# M162.net
KiCad netlist of a schematic drawn in EAGLE
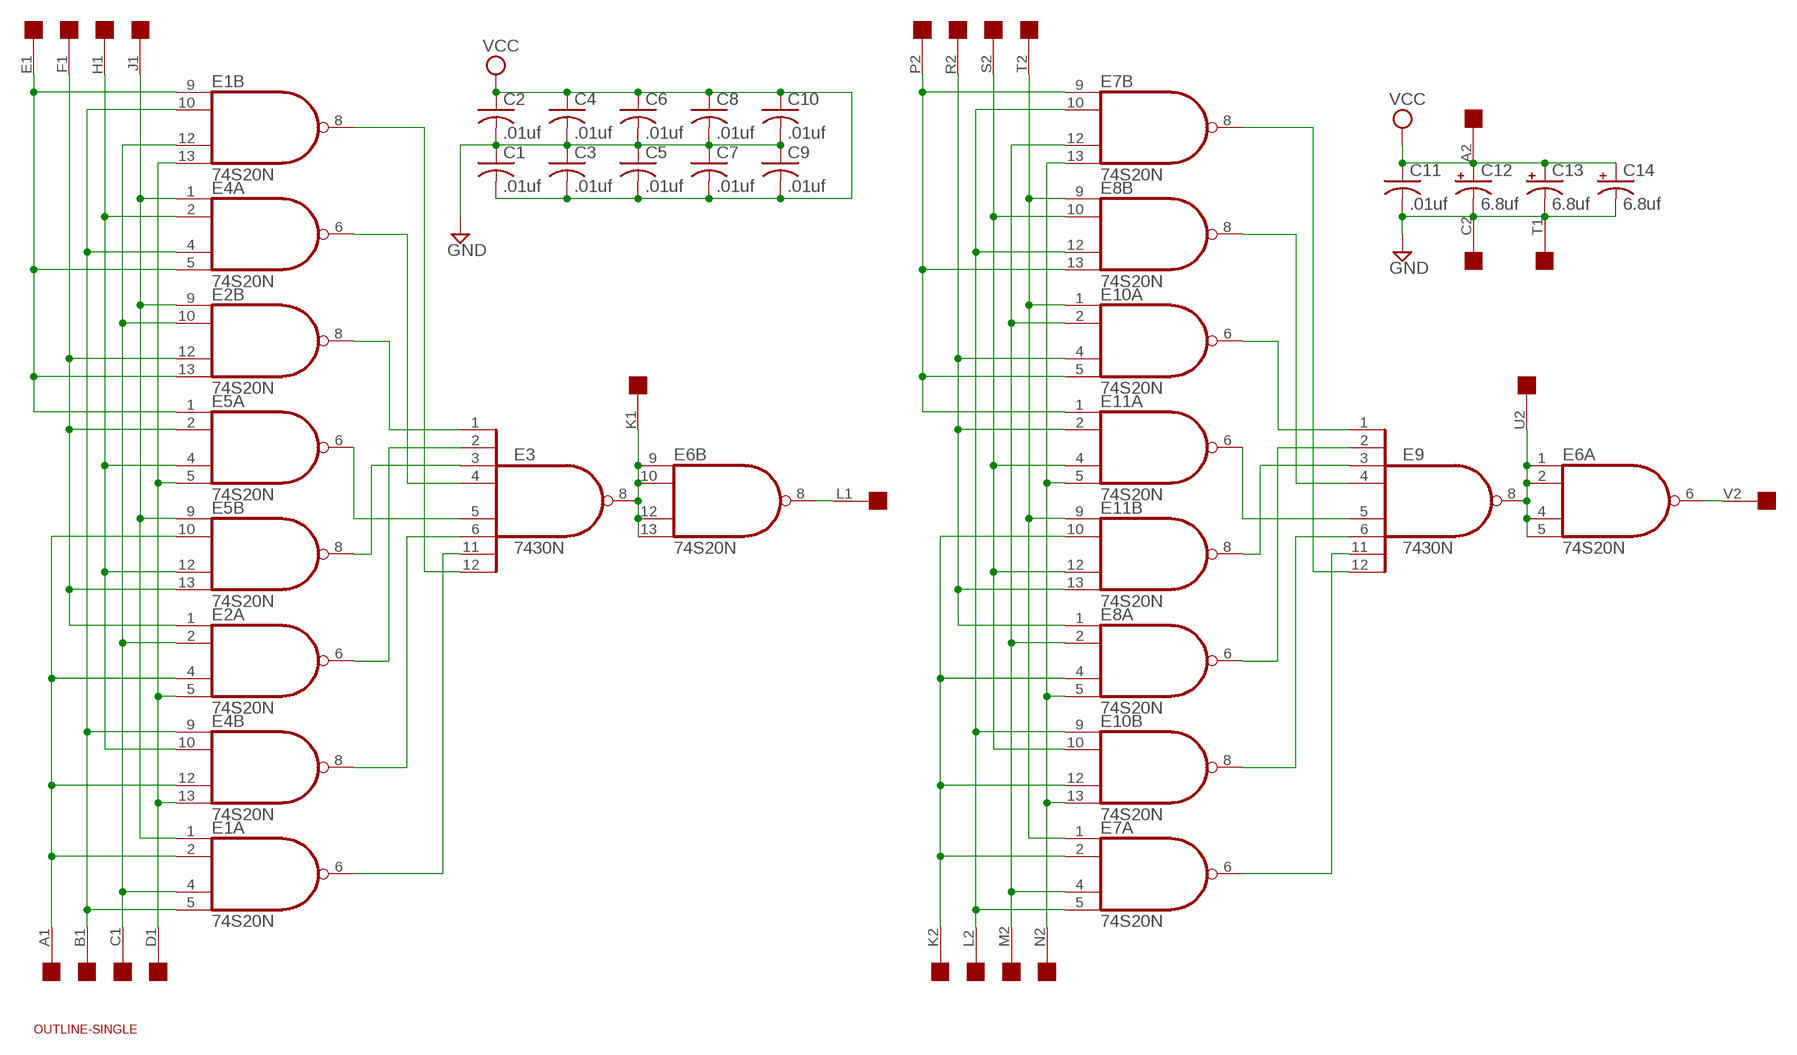
[diagram p0: schematic, sheet 1]

(export (version "E")
  (design (tool "Eeschema 10.0.6"))
  (components
    (comp (ref "C1")
      (value ".01uf")
      (footprint "eagle-import:C050-025X075")
      (libsource (lib "eagle-import") (part "C-US050-025X075"))
    )
    (comp (ref "C2")
      (value ".01uf")
      (footprint "eagle-import:C050-025X075")
      (libsource (lib "eagle-import") (part "C-US050-025X075"))
    )
    (comp (ref "C3")
      (value ".01uf")
      (footprint "eagle-import:C050-025X075")
      (libsource (lib "eagle-import") (part "C-US050-025X075"))
    )
    (comp (ref "C4")
      (value ".01uf")
      (footprint "eagle-import:C050-025X075")
      (libsource (lib "eagle-import") (part "C-US050-025X075"))
    )
    (comp (ref "C5")
      (value ".01uf")
      (footprint "eagle-import:C050-025X075")
      (libsource (lib "eagle-import") (part "C-US050-025X075"))
    )
    (comp (ref "C6")
      (value ".01uf")
      (footprint "eagle-import:C050-025X075")
      (libsource (lib "eagle-import") (part "C-US050-025X075"))
    )
    (comp (ref "C7")
      (value ".01uf")
      (footprint "eagle-import:C050-025X075")
      (libsource (lib "eagle-import") (part "C-US050-025X075"))
    )
    (comp (ref "C8")
      (value ".01uf")
      (footprint "eagle-import:C050-025X075")
      (libsource (lib "eagle-import") (part "C-US050-025X075"))
    )
    (comp (ref "C9")
      (value ".01uf")
      (footprint "eagle-import:C050-025X075")
      (libsource (lib "eagle-import") (part "C-US050-025X075"))
    )
    (comp (ref "C10")
      (value ".01uf")
      (footprint "eagle-import:C050-025X075")
      (libsource (lib "eagle-import") (part "C-US050-025X075"))
    )
    (comp (ref "C11")
      (value ".01uf")
      (footprint "eagle-import:C050-025X075")
      (libsource (lib "eagle-import") (part "C-US050-025X075"))
    )
    (comp (ref "C12")
      (value "6.8uf")
      (footprint "eagle-import:E22-6")
      (libsource (lib "eagle-import") (part "CPOL-USE22-6AXIAL"))
    )
    (comp (ref "C13")
      (value "6.8uf")
      (footprint "eagle-import:E22-6")
      (libsource (lib "eagle-import") (part "CPOL-USE22-6AXIAL"))
    )
    (comp (ref "C14")
      (value "6.8uf")
      (footprint "eagle-import:E22-6")
      (libsource (lib "eagle-import") (part "CPOL-USE22-6AXIAL"))
    )
    (comp (ref "E1")
      (value "74S20N")
      (footprint "eagle-import:DIL14")
      (libsource (lib "eagle-import") (part "7420NS"))
    )
    (comp (ref "E2")
      (value "74S20N")
      (footprint "eagle-import:DIL14")
      (libsource (lib "eagle-import") (part "7420NS"))
    )
    (comp (ref "E3")
      (value "7430N")
      (footprint "eagle-import:DIL14")
      (libsource (lib "eagle-import") (part "7430N"))
    )
    (comp (ref "E4")
      (value "74S20N")
      (footprint "eagle-import:DIL14")
      (libsource (lib "eagle-import") (part "7420NS"))
    )
    (comp (ref "E5")
      (value "74S20N")
      (footprint "eagle-import:DIL14")
      (libsource (lib "eagle-import") (part "7420NS"))
    )
    (comp (ref "E6")
      (value "74S20N")
      (footprint "eagle-import:DIL14")
      (libsource (lib "eagle-import") (part "7420NS"))
    )
    (comp (ref "E7")
      (value "74S20N")
      (footprint "eagle-import:DIL14")
      (libsource (lib "eagle-import") (part "7420NS"))
    )
    (comp (ref "E8")
      (value "74S20N")
      (footprint "eagle-import:DIL14")
      (libsource (lib "eagle-import") (part "7420NS"))
    )
    (comp (ref "E9")
      (value "7430N")
      (footprint "eagle-import:DIL14")
      (libsource (lib "eagle-import") (part "7430N"))
    )
    (comp (ref "E10")
      (value "74S20N")
      (footprint "eagle-import:DIL14")
      (libsource (lib "eagle-import") (part "7420NS"))
    )
    (comp (ref "E11")
      (value "74S20N")
      (footprint "eagle-import:DIL14")
      (libsource (lib "eagle-import") (part "7420NS"))
    )
    (comp (ref "U$1")
      (value "OUTLINE-SINGLE")
      (footprint "eagle-import:SINGLE")
      (libsource (lib "eagle-import") (part "OUTLINE-SINGLE"))
    )
    (comp (ref "U$2")
      (value "EDGE-2CONNECTOR")
      (footprint "eagle-import:EDGE-CON2")
      (libsource (lib "eagle-import") (part "EDGE-2CONNECTOR"))
    )
  )
  (nets
    (net (code "1") (name "GND") (class "Default")
      (node (ref "C1") (pin "1") (pinfunction "1_1") (pintype "passive"))
      (node (ref "C10") (pin "2") (pinfunction "2_2") (pintype "passive"))
      (node (ref "C11") (pin "2") (pinfunction "2_2") (pintype "passive"))
      (node (ref "C12") (pin "-") (pinfunction "-_-") (pintype "passive"))
      (node (ref "C13") (pin "-") (pinfunction "-_-") (pintype "passive"))
      (node (ref "C14") (pin "-") (pinfunction "-_-") (pintype "passive"))
      (node (ref "C2") (pin "2") (pinfunction "2_2") (pintype "passive"))
      (node (ref "C3") (pin "1") (pinfunction "1_1") (pintype "passive"))
      (node (ref "C4") (pin "2") (pinfunction "2_2") (pintype "passive"))
      (node (ref "C5") (pin "1") (pinfunction "1_1") (pintype "passive"))
      (node (ref "C6") (pin "2") (pinfunction "2_2") (pintype "passive"))
      (node (ref "C7") (pin "1") (pinfunction "1_1") (pintype "passive"))
      (node (ref "C8") (pin "2") (pinfunction "2_2") (pintype "passive"))
      (node (ref "C9") (pin "1") (pinfunction "1_1") (pintype "passive"))
      (node (ref "U$2") (pin "C2") (pinfunction "1_C2") (pintype "bidirectional"))
      (node (ref "U$2") (pin "T1") (pinfunction "1_T1") (pintype "bidirectional"))
    )
    (net (code "2") (name "Net-(E1A-I0)") (class "Default")
      (node (ref "E1") (pin "1") (pinfunction "I0_1") (pintype "input"))
      (node (ref "E2") (pin "9") (pinfunction "I0_9") (pintype "input"))
      (node (ref "E4") (pin "1") (pinfunction "I0_1") (pintype "input"))
      (node (ref "E5") (pin "9") (pinfunction "I0_9") (pintype "input"))
      (node (ref "U$2") (pin "J1") (pinfunction "1_J1") (pintype "bidirectional"))
    )
    (net (code "3") (name "Net-(E1A-I1)") (class "Default")
      (node (ref "E1") (pin "2") (pinfunction "I1_2") (pintype "input"))
      (node (ref "E2") (pin "4") (pinfunction "I2_4") (pintype "input"))
      (node (ref "E4") (pin "12") (pinfunction "I2_12") (pintype "input"))
      (node (ref "E5") (pin "10") (pinfunction "I1_10") (pintype "input"))
      (node (ref "U$2") (pin "A1") (pinfunction "1_A1") (pintype "bidirectional"))
    )
    (net (code "4") (name "Net-(E1A-I2)") (class "Default")
      (node (ref "E1") (pin "12") (pinfunction "I2_12") (pintype "input"))
      (node (ref "E1") (pin "4") (pinfunction "I2_4") (pintype "input"))
      (node (ref "E2") (pin "10") (pinfunction "I1_10") (pintype "input"))
      (node (ref "E2") (pin "2") (pinfunction "I1_2") (pintype "input"))
      (node (ref "U$2") (pin "C1") (pinfunction "1_C1") (pintype "bidirectional"))
    )
    (net (code "5") (name "Net-(E1A-I3)") (class "Default")
      (node (ref "E1") (pin "10") (pinfunction "I1_10") (pintype "input"))
      (node (ref "E1") (pin "5") (pinfunction "I3_5") (pintype "input"))
      (node (ref "E4") (pin "4") (pinfunction "I2_4") (pintype "input"))
      (node (ref "E4") (pin "9") (pinfunction "I0_9") (pintype "input"))
      (node (ref "U$2") (pin "B1") (pinfunction "1_B1") (pintype "bidirectional"))
    )
    (net (code "6") (name "Net-(E1A-O)") (class "Default")
      (node (ref "E1") (pin "6") (pinfunction "O_6") (pintype "output"))
      (node (ref "E3") (pin "11") (pinfunction "I6_11") (pintype "input"))
    )
    (net (code "7") (name "Net-(E1B-I0)") (class "Default")
      (node (ref "E1") (pin "9") (pinfunction "I0_9") (pintype "input"))
      (node (ref "E2") (pin "13") (pinfunction "I3_13") (pintype "input"))
      (node (ref "E4") (pin "5") (pinfunction "I3_5") (pintype "input"))
      (node (ref "E5") (pin "1") (pinfunction "I0_1") (pintype "input"))
      (node (ref "U$2") (pin "E1") (pinfunction "1_E1") (pintype "bidirectional"))
    )
    (net (code "8") (name "Net-(E1B-I3)") (class "Default")
      (node (ref "E1") (pin "13") (pinfunction "I3_13") (pintype "input"))
      (node (ref "E2") (pin "5") (pinfunction "I3_5") (pintype "input"))
      (node (ref "E4") (pin "13") (pinfunction "I3_13") (pintype "input"))
      (node (ref "E5") (pin "5") (pinfunction "I3_5") (pintype "input"))
      (node (ref "U$2") (pin "D1") (pinfunction "1_D1") (pintype "bidirectional"))
    )
    (net (code "9") (name "Net-(E1B-O)") (class "Default")
      (node (ref "E1") (pin "8") (pinfunction "O_8") (pintype "output"))
      (node (ref "E3") (pin "12") (pinfunction "I7_12") (pintype "input"))
    )
    (net (code "10") (name "Net-(E2A-I0)") (class "Default")
      (node (ref "E2") (pin "1") (pinfunction "I0_1") (pintype "input"))
      (node (ref "E2") (pin "12") (pinfunction "I2_12") (pintype "input"))
      (node (ref "E5") (pin "13") (pinfunction "I3_13") (pintype "input"))
      (node (ref "E5") (pin "2") (pinfunction "I1_2") (pintype "input"))
      (node (ref "U$2") (pin "F1") (pinfunction "1_F1") (pintype "bidirectional"))
    )
    (net (code "11") (name "Net-(E2A-O)") (class "Default")
      (node (ref "E2") (pin "6") (pinfunction "O_6") (pintype "output"))
      (node (ref "E3") (pin "2") (pinfunction "I1_2") (pintype "input"))
    )
    (net (code "12") (name "Net-(E2B-O)") (class "Default")
      (node (ref "E2") (pin "8") (pinfunction "O_8") (pintype "output"))
      (node (ref "E3") (pin "1") (pinfunction "I0_1") (pintype "input"))
    )
    (net (code "13") (name "Net-(E3A-I2)") (class "Default")
      (node (ref "E3") (pin "3") (pinfunction "I2_3") (pintype "input"))
      (node (ref "E5") (pin "8") (pinfunction "O_8") (pintype "output"))
    )
    (net (code "14") (name "Net-(E3A-I3)") (class "Default")
      (node (ref "E3") (pin "4") (pinfunction "I3_4") (pintype "input"))
      (node (ref "E4") (pin "6") (pinfunction "O_6") (pintype "output"))
    )
    (net (code "15") (name "Net-(E3A-I4)") (class "Default")
      (node (ref "E3") (pin "5") (pinfunction "I4_5") (pintype "input"))
      (node (ref "E5") (pin "6") (pinfunction "O_6") (pintype "output"))
    )
    (net (code "16") (name "Net-(E3A-I5)") (class "Default")
      (node (ref "E3") (pin "6") (pinfunction "I5_6") (pintype "input"))
      (node (ref "E4") (pin "8") (pinfunction "O_8") (pintype "output"))
    )
    (net (code "17") (name "Net-(E3A-O)") (class "Default")
      (node (ref "E3") (pin "8") (pinfunction "O_8") (pintype "output"))
      (node (ref "E6") (pin "10") (pinfunction "I1_10") (pintype "input"))
      (node (ref "E6") (pin "12") (pinfunction "I2_12") (pintype "input"))
      (node (ref "E6") (pin "13") (pinfunction "I3_13") (pintype "input"))
      (node (ref "E6") (pin "9") (pinfunction "I0_9") (pintype "input"))
      (node (ref "U$2") (pin "K1") (pinfunction "1_K1") (pintype "bidirectional"))
    )
    (net (code "18") (name "Net-(E4A-I1)") (class "Default")
      (node (ref "E4") (pin "10") (pinfunction "I1_10") (pintype "input"))
      (node (ref "E4") (pin "2") (pinfunction "I1_2") (pintype "input"))
      (node (ref "E5") (pin "12") (pinfunction "I2_12") (pintype "input"))
      (node (ref "E5") (pin "4") (pinfunction "I2_4") (pintype "input"))
      (node (ref "U$2") (pin "H1") (pinfunction "1_H1") (pintype "bidirectional"))
    )
    (net (code "19") (name "Net-(E6A-I0)") (class "Default")
      (node (ref "E6") (pin "1") (pinfunction "I0_1") (pintype "input"))
      (node (ref "E6") (pin "2") (pinfunction "I1_2") (pintype "input"))
      (node (ref "E6") (pin "4") (pinfunction "I2_4") (pintype "input"))
      (node (ref "E6") (pin "5") (pinfunction "I3_5") (pintype "input"))
      (node (ref "E9") (pin "8") (pinfunction "O_8") (pintype "output"))
      (node (ref "U$2") (pin "U2") (pinfunction "1_U2") (pintype "bidirectional"))
    )
    (net (code "20") (name "Net-(E6A-O)") (class "Default")
      (node (ref "E6") (pin "6") (pinfunction "O_6") (pintype "output"))
      (node (ref "U$2") (pin "V2") (pinfunction "1_V2") (pintype "bidirectional"))
    )
    (net (code "21") (name "Net-(E6B-O)") (class "Default")
      (node (ref "E6") (pin "8") (pinfunction "O_8") (pintype "output"))
      (node (ref "U$2") (pin "L1") (pinfunction "1_L1") (pintype "bidirectional"))
    )
    (net (code "22") (name "Net-(E7A-O)") (class "Default")
      (node (ref "E7") (pin "6") (pinfunction "O_6") (pintype "output"))
      (node (ref "E9") (pin "11") (pinfunction "I6_11") (pintype "input"))
    )
    (net (code "23") (name "Net-(E7B-O)") (class "Default")
      (node (ref "E7") (pin "8") (pinfunction "O_8") (pintype "output"))
      (node (ref "E9") (pin "12") (pinfunction "I7_12") (pintype "input"))
    )
    (net (code "24") (name "Net-(E8A-O)") (class "Default")
      (node (ref "E8") (pin "6") (pinfunction "O_6") (pintype "output"))
      (node (ref "E9") (pin "2") (pinfunction "I1_2") (pintype "input"))
    )
    (net (code "25") (name "Net-(E8B-O)") (class "Default")
      (node (ref "E8") (pin "8") (pinfunction "O_8") (pintype "output"))
      (node (ref "E9") (pin "4") (pinfunction "I3_4") (pintype "input"))
    )
    (net (code "26") (name "Net-(E10A-I0)") (class "Default")
      (node (ref "E10") (pin "1") (pinfunction "I0_1") (pintype "input"))
      (node (ref "E11") (pin "9") (pinfunction "I0_9") (pintype "input"))
      (node (ref "E7") (pin "1") (pinfunction "I0_1") (pintype "input"))
      (node (ref "E8") (pin "9") (pinfunction "I0_9") (pintype "input"))
      (node (ref "U$2") (pin "T2") (pinfunction "1_T2") (pintype "bidirectional"))
    )
    (net (code "27") (name "Net-(E10A-I1)") (class "Default")
      (node (ref "E10") (pin "2") (pinfunction "I1_2") (pintype "input"))
      (node (ref "E7") (pin "12") (pinfunction "I2_12") (pintype "input"))
      (node (ref "E7") (pin "4") (pinfunction "I2_4") (pintype "input"))
      (node (ref "E8") (pin "2") (pinfunction "I1_2") (pintype "input"))
      (node (ref "U$2") (pin "M2") (pinfunction "1_M2") (pintype "bidirectional"))
    )
    (net (code "28") (name "Net-(E10A-I2)") (class "Default")
      (node (ref "E10") (pin "4") (pinfunction "I2_4") (pintype "input"))
      (node (ref "E11") (pin "13") (pinfunction "I3_13") (pintype "input"))
      (node (ref "E11") (pin "2") (pinfunction "I1_2") (pintype "input"))
      (node (ref "E8") (pin "1") (pinfunction "I0_1") (pintype "input"))
      (node (ref "U$2") (pin "R2") (pinfunction "1_R2") (pintype "bidirectional"))
    )
    (net (code "29") (name "Net-(E10A-I3)") (class "Default")
      (node (ref "E10") (pin "5") (pinfunction "I3_5") (pintype "input"))
      (node (ref "E11") (pin "1") (pinfunction "I0_1") (pintype "input"))
      (node (ref "E7") (pin "9") (pinfunction "I0_9") (pintype "input"))
      (node (ref "E8") (pin "13") (pinfunction "I3_13") (pintype "input"))
      (node (ref "U$2") (pin "P2") (pinfunction "1_P2") (pintype "bidirectional"))
    )
    (net (code "30") (name "Net-(E10A-O)") (class "Default")
      (node (ref "E10") (pin "6") (pinfunction "O_6") (pintype "output"))
      (node (ref "E9") (pin "1") (pinfunction "I0_1") (pintype "input"))
    )
    (net (code "31") (name "Net-(E10B-I0)") (class "Default")
      (node (ref "E10") (pin "9") (pinfunction "I0_9") (pintype "input"))
      (node (ref "E7") (pin "10") (pinfunction "I1_10") (pintype "input"))
      (node (ref "E7") (pin "5") (pinfunction "I3_5") (pintype "input"))
      (node (ref "E8") (pin "12") (pinfunction "I2_12") (pintype "input"))
      (node (ref "U$2") (pin "L2") (pinfunction "1_L2") (pintype "bidirectional"))
    )
    (net (code "32") (name "Net-(E10B-I1)") (class "Default")
      (node (ref "E10") (pin "10") (pinfunction "I1_10") (pintype "input"))
      (node (ref "E11") (pin "12") (pinfunction "I2_12") (pintype "input"))
      (node (ref "E11") (pin "4") (pinfunction "I2_4") (pintype "input"))
      (node (ref "E8") (pin "10") (pinfunction "I1_10") (pintype "input"))
      (node (ref "U$2") (pin "S2") (pinfunction "1_S2") (pintype "bidirectional"))
    )
    (net (code "33") (name "Net-(E10B-I2)") (class "Default")
      (node (ref "E10") (pin "12") (pinfunction "I2_12") (pintype "input"))
      (node (ref "E11") (pin "10") (pinfunction "I1_10") (pintype "input"))
      (node (ref "E7") (pin "2") (pinfunction "I1_2") (pintype "input"))
      (node (ref "E8") (pin "4") (pinfunction "I2_4") (pintype "input"))
      (node (ref "U$2") (pin "K2") (pinfunction "1_K2") (pintype "bidirectional"))
    )
    (net (code "34") (name "Net-(E10B-I3)") (class "Default")
      (node (ref "E10") (pin "13") (pinfunction "I3_13") (pintype "input"))
      (node (ref "E11") (pin "5") (pinfunction "I3_5") (pintype "input"))
      (node (ref "E7") (pin "13") (pinfunction "I3_13") (pintype "input"))
      (node (ref "E8") (pin "5") (pinfunction "I3_5") (pintype "input"))
      (node (ref "U$2") (pin "N2") (pinfunction "1_N2") (pintype "bidirectional"))
    )
    (net (code "35") (name "Net-(E10B-O)") (class "Default")
      (node (ref "E10") (pin "8") (pinfunction "O_8") (pintype "output"))
      (node (ref "E9") (pin "6") (pinfunction "I5_6") (pintype "input"))
    )
    (net (code "36") (name "Net-(E11A-O)") (class "Default")
      (node (ref "E11") (pin "6") (pinfunction "O_6") (pintype "output"))
      (node (ref "E9") (pin "5") (pinfunction "I4_5") (pintype "input"))
    )
    (net (code "37") (name "Net-(E11B-O)") (class "Default")
      (node (ref "E11") (pin "8") (pinfunction "O_8") (pintype "output"))
      (node (ref "E9") (pin "3") (pinfunction "I2_3") (pintype "input"))
    )
    (net (code "38") (name "VCC") (class "Default")
      (node (ref "C1") (pin "2") (pinfunction "2_2") (pintype "passive"))
      (node (ref "C10") (pin "1") (pinfunction "1_1") (pintype "passive"))
      (node (ref "C11") (pin "1") (pinfunction "1_1") (pintype "passive"))
      (node (ref "C12") (pin "+") (pinfunction "+_+") (pintype "passive"))
      (node (ref "C13") (pin "+") (pinfunction "+_+") (pintype "passive"))
      (node (ref "C14") (pin "+") (pinfunction "+_+") (pintype "passive"))
      (node (ref "C2") (pin "1") (pinfunction "1_1") (pintype "passive"))
      (node (ref "C3") (pin "2") (pinfunction "2_2") (pintype "passive"))
      (node (ref "C4") (pin "1") (pinfunction "1_1") (pintype "passive"))
      (node (ref "C5") (pin "2") (pinfunction "2_2") (pintype "passive"))
      (node (ref "C6") (pin "1") (pinfunction "1_1") (pintype "passive"))
      (node (ref "C7") (pin "2") (pinfunction "2_2") (pintype "passive"))
      (node (ref "C8") (pin "1") (pinfunction "1_1") (pintype "passive"))
      (node (ref "C9") (pin "2") (pinfunction "2_2") (pintype "passive"))
      (node (ref "U$2") (pin "A2") (pinfunction "1_A2") (pintype "bidirectional"))
    )
  )
)
